# Microboard_PCB.net
KiCad netlist of a schematic drawn in EAGLE
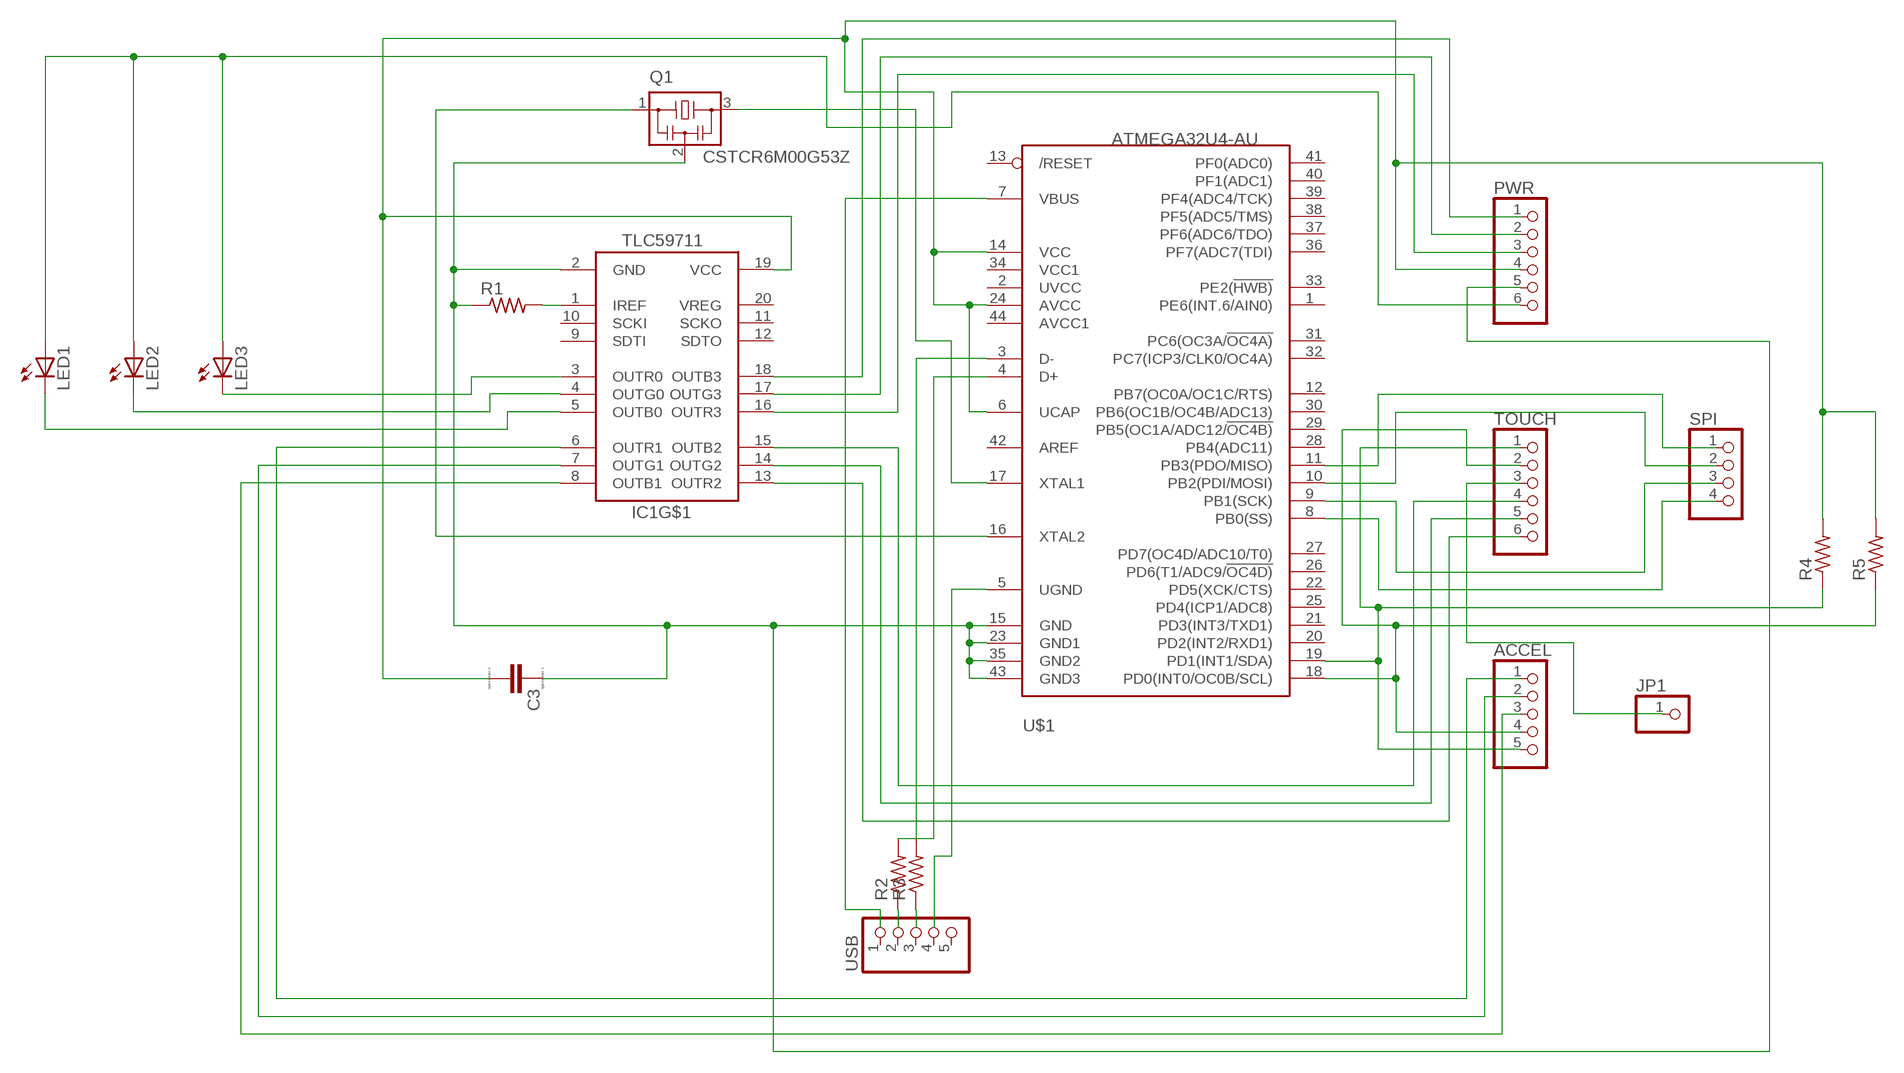
[diagram p0: schematic, sheet 1]

(export (version "E")
  (design (tool "Eeschema 10.0.6"))
  (components
    (comp (ref "ACCEL")
      (value "PINHD-1X5")
      (footprint "eagle-import:1X05")
      (libsource (lib "eagle-import") (part "PINHD-1X5"))
    )
    (comp (ref "C3")
      (value "CC0603")
      (footprint "eagle-import:C0603")
      (libsource (lib "eagle-import") (part "CC0603"))
    )
    (comp (ref "IC1")
      (value "TLC59711")
      (footprint "eagle-import:HTSSOP20DAP")
      (libsource (lib "eagle-import") (part "TLC59711"))
    )
    (comp (ref "JP1")
      (value "PINHD-1X1")
      (footprint "eagle-import:1X01")
      (libsource (lib "eagle-import") (part "PINHD-1X1"))
    )
    (comp (ref "LED1")
      (value "LEDP-LCC-4")
      (footprint "eagle-import:P-LCC-4")
      (libsource (lib "eagle-import") (part "LEDP-LCC-4"))
    )
    (comp (ref "LED2")
      (value "LEDP-LCC-4")
      (footprint "eagle-import:P-LCC-4")
      (libsource (lib "eagle-import") (part "LEDP-LCC-4"))
    )
    (comp (ref "LED3")
      (value "LEDP-LCC-4")
      (footprint "eagle-import:P-LCC-4")
      (libsource (lib "eagle-import") (part "LEDP-LCC-4"))
    )
    (comp (ref "PWR")
      (value "PINHD-1X6")
      (footprint "eagle-import:1X06")
      (libsource (lib "eagle-import") (part "PINHD-1X6"))
    )
    (comp (ref "Q1")
      (value "CSTCR6M00G53Z")
      (footprint "eagle-import:CSTCR6M")
      (fields (field (name "MPN") "CSTCR6M00G53-R0"))
      (libsource (lib "eagle-import") (part "CSTCR6M00G53Z"))
    )
    (comp (ref "R1")
      (value "R-US_R0805")
      (footprint "eagle-import:R0805")
      (libsource (lib "eagle-import") (part "R-US_R0805"))
    )
    (comp (ref "R2")
      (value "R-US_R0805")
      (footprint "eagle-import:R0805")
      (libsource (lib "eagle-import") (part "R-US_R0805"))
    )
    (comp (ref "R3")
      (value "R-US_R0805")
      (footprint "eagle-import:R0805")
      (libsource (lib "eagle-import") (part "R-US_R0805"))
    )
    (comp (ref "R4")
      (value "R-US_R0805")
      (footprint "eagle-import:R0805")
      (libsource (lib "eagle-import") (part "R-US_R0805"))
    )
    (comp (ref "R5")
      (value "R-US_R0805")
      (footprint "eagle-import:R0805")
      (libsource (lib "eagle-import") (part "R-US_R0805"))
    )
    (comp (ref "SPI")
      (value "PINHD-1X4")
      (footprint "eagle-import:1X04")
      (libsource (lib "eagle-import") (part "PINHD-1X4"))
    )
    (comp (ref "TOUCH")
      (value "PINHD-1X6")
      (footprint "eagle-import:1X06")
      (libsource (lib "eagle-import") (part "PINHD-1X6"))
    )
    (comp (ref "U$1")
      (value "ATMEGA32U4-AU")
      (footprint "eagle-import:TQFP44")
      (libsource (lib "eagle-import") (part "ATMEGA32U4-AU"))
    )
    (comp (ref "USB")
      (value "PINHD-1X5")
      (footprint "eagle-import:1X05")
      (libsource (lib "eagle-import") (part "PINHD-1X5"))
    )
  )
  (nets
    (net (code "1") (name "Net-(IC1A-GND)") (class "Default")
      (node (ref "C3") (pin "1") (pinfunction "1_1") (pintype "passive"))
      (node (ref "IC1") (pin "2") (pinfunction "GND_2") (pintype "power_in"))
      (node (ref "PWR") (pin "5") (pinfunction "5_5") (pintype "passive"))
      (node (ref "Q1") (pin "2") (pinfunction "2_2") (pintype "passive"))
      (node (ref "R1") (pin "1") (pinfunction "1_1") (pintype "passive"))
      (node (ref "U$1") (pin "15") (pinfunction "GND_15") (pintype "bidirectional"))
      (node (ref "U$1") (pin "23") (pinfunction "GND1_23") (pintype "bidirectional"))
      (node (ref "U$1") (pin "35") (pinfunction "GND2_35") (pintype "bidirectional"))
      (node (ref "U$1") (pin "43") (pinfunction "GND3_43") (pintype "bidirectional"))
    )
    (net (code "2") (name "Net-(IC1A-IREF)") (class "Default")
      (node (ref "IC1") (pin "1") (pinfunction "IREF_1") (pintype "bidirectional"))
      (node (ref "R1") (pin "2") (pinfunction "2_2") (pintype "passive"))
    )
    (net (code "3") (name "Net-(IC1A-OUTB0)") (class "Default")
      (node (ref "IC1") (pin "5") (pinfunction "OUTB0_5") (pintype "open_collector"))
      (node (ref "LED1") (pin "C@4") (pinfunction "C_C@4") (pintype "passive"))
    )
    (net (code "4") (name "Net-(IC1A-OUTB1)") (class "Default")
      (node (ref "ACCEL") (pin "3") (pinfunction "3_3") (pintype "passive"))
      (node (ref "IC1") (pin "8") (pinfunction "OUTB1_8") (pintype "open_collector"))
    )
    (net (code "5") (name "Net-(IC1A-OUTB2)") (class "Default")
      (node (ref "IC1") (pin "15") (pinfunction "OUTB2_15") (pintype "open_collector"))
      (node (ref "TOUCH") (pin "4") (pinfunction "4_4") (pintype "passive"))
    )
    (net (code "6") (name "Net-(IC1A-OUTB3)") (class "Default")
      (node (ref "IC1") (pin "18") (pinfunction "OUTB3_18") (pintype "open_collector"))
      (node (ref "PWR") (pin "1") (pinfunction "1_1") (pintype "passive"))
    )
    (net (code "7") (name "Net-(IC1A-OUTG0)") (class "Default")
      (node (ref "IC1") (pin "4") (pinfunction "OUTG0_4") (pintype "open_collector"))
      (node (ref "LED2") (pin "C@4") (pinfunction "C_C@4") (pintype "passive"))
    )
    (net (code "8") (name "Net-(IC1A-OUTG1)") (class "Default")
      (node (ref "ACCEL") (pin "2") (pinfunction "2_2") (pintype "passive"))
      (node (ref "IC1") (pin "7") (pinfunction "OUTG1_7") (pintype "open_collector"))
    )
    (net (code "9") (name "Net-(IC1A-OUTG2)") (class "Default")
      (node (ref "IC1") (pin "14") (pinfunction "OUTG2_14") (pintype "open_collector"))
      (node (ref "TOUCH") (pin "5") (pinfunction "5_5") (pintype "passive"))
    )
    (net (code "10") (name "Net-(IC1A-OUTG3)") (class "Default")
      (node (ref "IC1") (pin "17") (pinfunction "OUTG3_17") (pintype "open_collector"))
      (node (ref "PWR") (pin "2") (pinfunction "2_2") (pintype "passive"))
    )
    (net (code "11") (name "Net-(IC1A-OUTR0)") (class "Default")
      (node (ref "IC1") (pin "3") (pinfunction "OUTR0_3") (pintype "open_collector"))
      (node (ref "LED3") (pin "C@4") (pinfunction "C_C@4") (pintype "passive"))
    )
    (net (code "12") (name "Net-(IC1A-OUTR1)") (class "Default")
      (node (ref "ACCEL") (pin "1") (pinfunction "1_1") (pintype "passive"))
      (node (ref "IC1") (pin "6") (pinfunction "OUTR1_6") (pintype "open_collector"))
    )
    (net (code "13") (name "Net-(IC1A-OUTR2)") (class "Default")
      (node (ref "IC1") (pin "13") (pinfunction "OUTR2_13") (pintype "open_collector"))
      (node (ref "TOUCH") (pin "6") (pinfunction "6_6") (pintype "passive"))
    )
    (net (code "14") (name "Net-(IC1A-OUTR3)") (class "Default")
      (node (ref "IC1") (pin "16") (pinfunction "OUTR3_16") (pintype "open_collector"))
      (node (ref "PWR") (pin "3") (pinfunction "3_3") (pintype "passive"))
    )
    (net (code "15") (name "Net-(IC1A-VCC)") (class "Default")
      (node (ref "C3") (pin "2") (pinfunction "2_2") (pintype "passive"))
      (node (ref "IC1") (pin "19") (pinfunction "VCC_19") (pintype "power_in"))
      (node (ref "PWR") (pin "4") (pinfunction "4_4") (pintype "passive"))
      (node (ref "R4") (pin "2") (pinfunction "2_2") (pintype "passive"))
      (node (ref "R5") (pin "2") (pinfunction "2_2") (pintype "passive"))
      (node (ref "U$1") (pin "14") (pinfunction "VCC_14") (pintype "bidirectional"))
      (node (ref "U$1") (pin "24") (pinfunction "AVCC_24") (pintype "bidirectional"))
      (node (ref "U$1") (pin "6") (pinfunction "UCAP_6") (pintype "bidirectional"))
    )
    (net (code "16") (name "Net-(JP1-Pad1)") (class "Default")
      (node (ref "JP1") (pin "1") (pinfunction "1_1") (pintype "passive"))
      (node (ref "TOUCH") (pin "3") (pinfunction "3_3") (pintype "passive"))
    )
    (net (code "17") (name "Net-(LED1-PadA)") (class "Default")
      (node (ref "LED1") (pin "A") (pinfunction "A_A") (pintype "passive"))
      (node (ref "LED2") (pin "A") (pinfunction "A_A") (pintype "passive"))
      (node (ref "LED3") (pin "A") (pinfunction "A_A") (pintype "passive"))
      (node (ref "PWR") (pin "6") (pinfunction "6_6") (pintype "passive"))
    )
    (net (code "18") (name "Net-(U$1-D+)") (class "Default")
      (node (ref "R2") (pin "2") (pinfunction "2_2") (pintype "passive"))
      (node (ref "U$1") (pin "4") (pinfunction "D+_4") (pintype "bidirectional"))
    )
    (net (code "19") (name "Net-(U$1-D-)") (class "Default")
      (node (ref "R3") (pin "2") (pinfunction "2_2") (pintype "passive"))
      (node (ref "U$1") (pin "3") (pinfunction "D-_3") (pintype "bidirectional"))
    )
    (net (code "20") (name "Net-(U$1-PB0(SS))") (class "Default")
      (node (ref "SPI") (pin "4") (pinfunction "4_4") (pintype "passive"))
      (node (ref "U$1") (pin "8") (pinfunction "PB0(SS)_8") (pintype "bidirectional"))
    )
    (net (code "21") (name "Net-(U$1-PB1(SCK))") (class "Default")
      (node (ref "SPI") (pin "3") (pinfunction "3_3") (pintype "passive"))
      (node (ref "U$1") (pin "9") (pinfunction "PB1(SCK)_9") (pintype "bidirectional"))
    )
    (net (code "22") (name "Net-(U$1-PB2(PDI{slash}MOSI))") (class "Default")
      (node (ref "SPI") (pin "2") (pinfunction "2_2") (pintype "passive"))
      (node (ref "U$1") (pin "10") (pinfunction "PB2(PDI/MOSI)_10") (pintype "bidirectional"))
    )
    (net (code "23") (name "Net-(U$1-PB3(PDO{slash}MISO))") (class "Default")
      (node (ref "SPI") (pin "1") (pinfunction "1_1") (pintype "passive"))
      (node (ref "U$1") (pin "11") (pinfunction "PB3(PDO/MISO)_11") (pintype "bidirectional"))
    )
    (net (code "24") (name "Net-(U$1-PD0(INT0{slash}OC0B{slash}SCL))") (class "Default")
      (node (ref "ACCEL") (pin "4") (pinfunction "4_4") (pintype "passive"))
      (node (ref "R5") (pin "1") (pinfunction "1_1") (pintype "passive"))
      (node (ref "TOUCH") (pin "2") (pinfunction "2_2") (pintype "passive"))
      (node (ref "U$1") (pin "18") (pinfunction "PD0(INT0/OC0B/SCL)_18") (pintype "bidirectional"))
    )
    (net (code "25") (name "Net-(U$1-PD1(INT1{slash}SDA))") (class "Default")
      (node (ref "ACCEL") (pin "5") (pinfunction "5_5") (pintype "passive"))
      (node (ref "R4") (pin "1") (pinfunction "1_1") (pintype "passive"))
      (node (ref "TOUCH") (pin "1") (pinfunction "1_1") (pintype "passive"))
      (node (ref "U$1") (pin "19") (pinfunction "PD1(INT1/SDA)_19") (pintype "bidirectional"))
    )
    (net (code "26") (name "Net-(U$1-XTAL1)") (class "Default")
      (node (ref "Q1") (pin "3") (pinfunction "3_3") (pintype "passive"))
      (node (ref "U$1") (pin "17") (pinfunction "XTAL1_17") (pintype "bidirectional"))
    )
    (net (code "27") (name "Net-(U$1-XTAL2)") (class "Default")
      (node (ref "Q1") (pin "1") (pinfunction "1_1") (pintype "passive"))
      (node (ref "U$1") (pin "16") (pinfunction "XTAL2_16") (pintype "bidirectional"))
    )
    (net (code "28") (name "unconnected-(IC1A-SCKI-Pad10)") (class "Default")
      (node (ref "IC1") (pin "10") (pinfunction "SCKI_10") (pintype "input"))
    )
    (net (code "29") (name "unconnected-(IC1A-SCKO-Pad11)") (class "Default")
      (node (ref "IC1") (pin "11") (pinfunction "SCKO_11") (pintype "output"))
    )
    (net (code "30") (name "unconnected-(IC1A-SDTI-Pad9)") (class "Default")
      (node (ref "IC1") (pin "9") (pinfunction "SDTI_9") (pintype "input"))
    )
    (net (code "31") (name "unconnected-(IC1A-SDTO-Pad12)") (class "Default")
      (node (ref "IC1") (pin "12") (pinfunction "SDTO_12") (pintype "output"))
    )
    (net (code "32") (name "unconnected-(IC1A-VREG-Pad20)") (class "Default")
      (node (ref "IC1") (pin "20") (pinfunction "VREG_20") (pintype "bidirectional"))
    )
    (net (code "33") (name "unconnected-(R2-Pad1)") (class "Default")
      (node (ref "R2") (pin "1") (pinfunction "1_1") (pintype "passive"))
    )
    (net (code "34") (name "unconnected-(R3-Pad1)") (class "Default")
      (node (ref "R3") (pin "1") (pinfunction "1_1") (pintype "passive"))
    )
    (net (code "35") (name "unconnected-(U$1-AREF-Pad42)") (class "Default")
      (node (ref "U$1") (pin "42") (pinfunction "AREF_42") (pintype "bidirectional"))
    )
    (net (code "36") (name "unconnected-(U$1-AVCC1-Pad44)") (class "Default")
      (node (ref "U$1") (pin "44") (pinfunction "AVCC1_44") (pintype "bidirectional"))
    )
    (net (code "37") (name "unconnected-(U$1-PB4(ADC11)-Pad28)") (class "Default")
      (node (ref "U$1") (pin "28") (pinfunction "PB4(ADC11)_28") (pintype "bidirectional"))
    )
    (net (code "38") (name "unconnected-(U$1-PB5(OC1A{slash}ADC12{slash}~{OC4B})-Pad29)") (class "Default")
      (node (ref "U$1") (pin "29") (pinfunction "PB5(OC1A/ADC12/~{OC4B})_29") (pintype "bidirectional"))
    )
    (net (code "39") (name "unconnected-(U$1-PB6(OC1B{slash}OC4B{slash}ADC13)-Pad30)") (class "Default")
      (node (ref "U$1") (pin "30") (pinfunction "PB6(OC1B/OC4B/ADC13)_30") (pintype "bidirectional"))
    )
    (net (code "40") (name "unconnected-(U$1-PB7(OC0A{slash}OC1C{slash}RTS)-Pad12)") (class "Default")
      (node (ref "U$1") (pin "12") (pinfunction "PB7(OC0A/OC1C/RTS)_12") (pintype "bidirectional"))
    )
    (net (code "41") (name "unconnected-(U$1-PC6(OC3A{slash}~{OC4A})-Pad31)") (class "Default")
      (node (ref "U$1") (pin "31") (pinfunction "PC6(OC3A/~{OC4A})_31") (pintype "bidirectional"))
    )
    (net (code "42") (name "unconnected-(U$1-PC7(ICP3{slash}CLK0{slash}OC4A)-Pad32)") (class "Default")
      (node (ref "U$1") (pin "32") (pinfunction "PC7(ICP3/CLK0/OC4A)_32") (pintype "bidirectional"))
    )
    (net (code "43") (name "unconnected-(U$1-PD2(INT2{slash}RXD1)-Pad20)") (class "Default")
      (node (ref "U$1") (pin "20") (pinfunction "PD2(INT2/RXD1)_20") (pintype "bidirectional"))
    )
    (net (code "44") (name "unconnected-(U$1-PD3(INT3{slash}TXD1)-Pad21)") (class "Default")
      (node (ref "U$1") (pin "21") (pinfunction "PD3(INT3/TXD1)_21") (pintype "bidirectional"))
    )
    (net (code "45") (name "unconnected-(U$1-PD4(ICP1{slash}ADC8)-Pad25)") (class "Default")
      (node (ref "U$1") (pin "25") (pinfunction "PD4(ICP1/ADC8)_25") (pintype "bidirectional"))
    )
    (net (code "46") (name "unconnected-(U$1-PD5(XCK{slash}CTS)-Pad22)") (class "Default")
      (node (ref "U$1") (pin "22") (pinfunction "PD5(XCK/CTS)_22") (pintype "bidirectional"))
    )
    (net (code "47") (name "unconnected-(U$1-PD6(T1{slash}ADC9{slash}~{OC4D})-Pad26)") (class "Default")
      (node (ref "U$1") (pin "26") (pinfunction "PD6(T1/ADC9/~{OC4D})_26") (pintype "bidirectional"))
    )
    (net (code "48") (name "unconnected-(U$1-PD7(OC4D{slash}ADC10{slash}T0)-Pad27)") (class "Default")
      (node (ref "U$1") (pin "27") (pinfunction "PD7(OC4D/ADC10/T0)_27") (pintype "bidirectional"))
    )
    (net (code "49") (name "unconnected-(U$1-PE2(~{HWB})-Pad33)") (class "Default")
      (node (ref "U$1") (pin "33") (pinfunction "PE2(~{HWB})_33") (pintype "bidirectional"))
    )
    (net (code "50") (name "unconnected-(U$1-PE6(INT.6{slash}AIN0)-Pad1)") (class "Default")
      (node (ref "U$1") (pin "1") (pinfunction "PE6(INT.6/AIN0)_1") (pintype "bidirectional"))
    )
    (net (code "51") (name "unconnected-(U$1-PF0(ADC0)-Pad41)") (class "Default")
      (node (ref "U$1") (pin "41") (pinfunction "PF0(ADC0)_41") (pintype "bidirectional"))
    )
    (net (code "52") (name "unconnected-(U$1-PF1(ADC1)-Pad40)") (class "Default")
      (node (ref "U$1") (pin "40") (pinfunction "PF1(ADC1)_40") (pintype "bidirectional"))
    )
    (net (code "53") (name "unconnected-(U$1-PF4(ADC4{slash}TCK)-Pad39)") (class "Default")
      (node (ref "U$1") (pin "39") (pinfunction "PF4(ADC4/TCK)_39") (pintype "bidirectional"))
    )
    (net (code "54") (name "unconnected-(U$1-PF5(ADC5{slash}TMS)-Pad38)") (class "Default")
      (node (ref "U$1") (pin "38") (pinfunction "PF5(ADC5/TMS)_38") (pintype "bidirectional"))
    )
    (net (code "55") (name "unconnected-(U$1-PF6(ADC6{slash}TDO)-Pad37)") (class "Default")
      (node (ref "U$1") (pin "37") (pinfunction "PF6(ADC6/TDO)_37") (pintype "bidirectional"))
    )
    (net (code "56") (name "unconnected-(U$1-PF7(ADC7(TDI)-Pad36)") (class "Default")
      (node (ref "U$1") (pin "36") (pinfunction "PF7(ADC7(TDI)_36") (pintype "bidirectional"))
    )
    (net (code "57") (name "unconnected-(U$1-UGND-Pad5)") (class "Default")
      (node (ref "U$1") (pin "5") (pinfunction "UGND_5") (pintype "bidirectional"))
    )
    (net (code "58") (name "unconnected-(U$1-UVCC-Pad2)") (class "Default")
      (node (ref "U$1") (pin "2") (pinfunction "UVCC_2") (pintype "bidirectional"))
    )
    (net (code "59") (name "unconnected-(U$1-VBUS-Pad7)") (class "Default")
      (node (ref "U$1") (pin "7") (pinfunction "VBUS_7") (pintype "bidirectional"))
    )
    (net (code "60") (name "unconnected-(U$1-VCC1-Pad34)") (class "Default")
      (node (ref "U$1") (pin "34") (pinfunction "VCC1_34") (pintype "bidirectional"))
    )
    (net (code "61") (name "unconnected-(U$1-{slash}RESET-Pad13)") (class "Default")
      (node (ref "U$1") (pin "13") (pinfunction "/RESET_13") (pintype "bidirectional"))
    )
    (net (code "62") (name "unconnected-(USB-Pad1)") (class "Default")
      (node (ref "USB") (pin "1") (pinfunction "1_1") (pintype "passive"))
    )
    (net (code "63") (name "unconnected-(USB-Pad2)") (class "Default")
      (node (ref "USB") (pin "2") (pinfunction "2_2") (pintype "passive"))
    )
    (net (code "64") (name "unconnected-(USB-Pad3)") (class "Default")
      (node (ref "USB") (pin "3") (pinfunction "3_3") (pintype "passive"))
    )
    (net (code "65") (name "unconnected-(USB-Pad4)") (class "Default")
      (node (ref "USB") (pin "4") (pinfunction "4_4") (pintype "passive"))
    )
    (net (code "66") (name "unconnected-(USB-Pad5)") (class "Default")
      (node (ref "USB") (pin "5") (pinfunction "5_5") (pintype "passive"))
    )
  )
)
